# minimal-atmega32u4-arduino.net
KiCad netlist of a schematic drawn in EAGLE
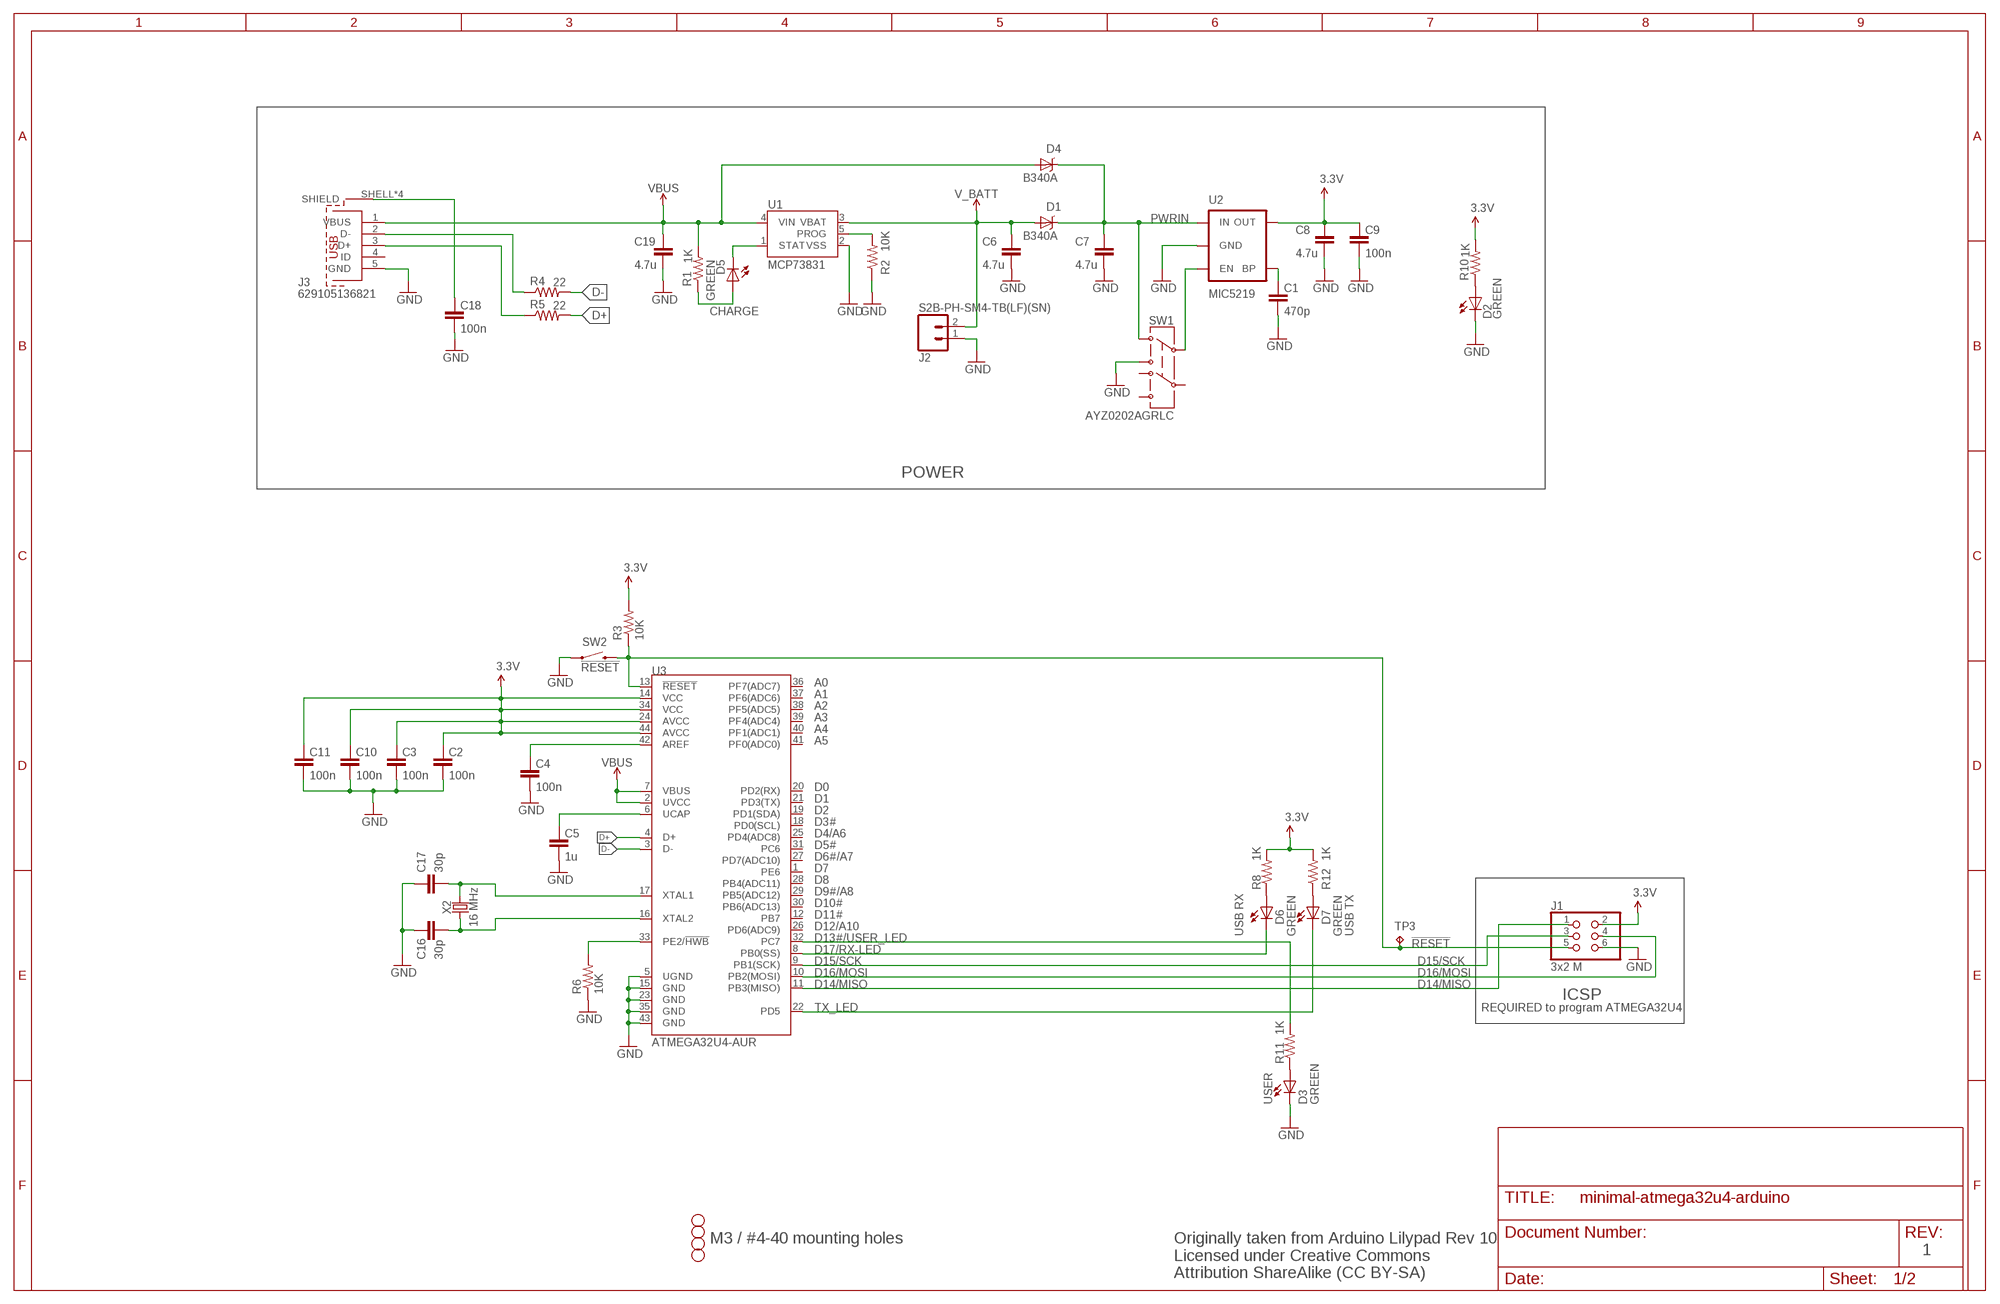
[diagram p0: schematic, sheet 1]

(export (version "E")
  (design (tool "Eeschema 10.0.6"))
  (components
    (comp (ref "C1")
      (value "470p")
      (footprint "eagle-import:C0805K")
      (fields (field (name "MFR") "Samsung") (field (name "MPN") "CL21B471KBANNNC"))
      (libsource (lib "eagle-import") (part "C-EUC0805K"))
    )
    (comp (ref "C2")
      (value "100n")
      (footprint "eagle-import:C0805K")
      (fields (field (name "MFR") "Samsung") (field (name "MPN") "CL21B104KBCNNNC"))
      (libsource (lib "eagle-import") (part "C-EUC0805K"))
    )
    (comp (ref "C3")
      (value "100n")
      (footprint "eagle-import:C0805K")
      (fields (field (name "MFR") "Samsung") (field (name "MPN") "CL21B104KBCNNNC"))
      (libsource (lib "eagle-import") (part "C-EUC0805K"))
    )
    (comp (ref "C4")
      (value "100n")
      (footprint "eagle-import:C0805K")
      (fields (field (name "MFR") "Samsung") (field (name "MPN") "CL21B104KBCNNNC"))
      (libsource (lib "eagle-import") (part "C-EUC0805K"))
    )
    (comp (ref "C5")
      (value "1u")
      (footprint "eagle-import:C0805K")
      (fields (field (name "MFR") "Samsung") (field (name "MPN") "CL21B105KOFNNNG"))
      (libsource (lib "eagle-import") (part "C-EUC0805K"))
    )
    (comp (ref "C6")
      (value "4.7u")
      (footprint "eagle-import:C0805K")
      (fields (field (name "MFR") "Samsung") (field (name "MPN") "CL21A475KOFNNNE"))
      (libsource (lib "eagle-import") (part "C-EUC0805K"))
    )
    (comp (ref "C7")
      (value "4.7u")
      (footprint "eagle-import:C0805K")
      (fields (field (name "MFR") "Samsung") (field (name "MPN") "CL21A475KOFNNNE"))
      (libsource (lib "eagle-import") (part "C-EUC0805K"))
    )
    (comp (ref "C8")
      (value "4.7u")
      (footprint "eagle-import:C0805K")
      (fields (field (name "MFR") "Samsung") (field (name "MPN") "CL21A475KOFNNNE"))
      (libsource (lib "eagle-import") (part "C-EUC0805K"))
    )
    (comp (ref "C9")
      (value "100n")
      (footprint "eagle-import:C0805K")
      (fields (field (name "MFR") "Samsung") (field (name "MPN") "CL21B104KBCNNNC"))
      (libsource (lib "eagle-import") (part "C-EUC0805K"))
    )
    (comp (ref "C10")
      (value "100n")
      (footprint "eagle-import:C0805K")
      (fields (field (name "MFR") "Samsung") (field (name "MPN") "CL21B104KBCNNNC"))
      (libsource (lib "eagle-import") (part "C-EUC0805K"))
    )
    (comp (ref "C11")
      (value "100n")
      (footprint "eagle-import:C0805K")
      (fields (field (name "MFR") "Samsung") (field (name "MPN") "CL21B104KBCNNNC"))
      (libsource (lib "eagle-import") (part "C-EUC0805K"))
    )
    (comp (ref "C16")
      (value "30p")
      (footprint "eagle-import:C0805K")
      (fields (field (name "MFR") "Samsung") (field (name "MPN") "CL21C300JBANNNC"))
      (libsource (lib "eagle-import") (part "C-EUC0805K"))
    )
    (comp (ref "C17")
      (value "30p")
      (footprint "eagle-import:C0805K")
      (fields (field (name "MFR") "Samsung") (field (name "MPN") "CL21C180JBANNNC"))
      (libsource (lib "eagle-import") (part "C-EUC0805K"))
    )
    (comp (ref "C18")
      (value "100n")
      (footprint "eagle-import:C0805K")
      (fields (field (name "MFR") "Samsung") (field (name "MPN") "CL21B104KBCNNNC"))
      (libsource (lib "eagle-import") (part "C-EUC0805K"))
    )
    (comp (ref "C19")
      (value "4.7u")
      (footprint "eagle-import:C0805K")
      (fields (field (name "MFR") "Samsung") (field (name "MPN") "CL21A475KOFNNNE"))
      (libsource (lib "eagle-import") (part "C-EUC0805K"))
    )
    (comp (ref "D1")
      (value "B340A")
      (footprint "eagle-import:SMA-DIODE")
      (fields (field (name "MFR") "Diodes Inc") (field (name "MPN") "B340AE-13"))
      (libsource (lib "eagle-import") (part "DIODE-SCHOTTKY_"))
    )
    (comp (ref "D2")
      (value "GREEN")
      (footprint "eagle-import:CHIP-LED0805")
      (fields (field (name "MFR") "Würth Elektronik") (field (name "MPN") "150080GS75000"))
      (libsource (lib "eagle-import") (part "LEDCHIP-LED0805"))
    )
    (comp (ref "D3")
      (value "GREEN")
      (footprint "eagle-import:CHIP-LED0805")
      (fields (field (name "MFR") "Würth Elektronik") (field (name "MPN") "150080GS75000"))
      (libsource (lib "eagle-import") (part "LEDCHIP-LED0805"))
    )
    (comp (ref "D4")
      (value "B340A")
      (footprint "eagle-import:SMA-DIODE")
      (fields (field (name "MFR") "Diodes Inc") (field (name "MPN") "B340AE-13"))
      (libsource (lib "eagle-import") (part "DIODE-SCHOTTKY_"))
    )
    (comp (ref "D5")
      (value "GREEN")
      (footprint "eagle-import:CHIP-LED0805")
      (fields (field (name "MFR") "Würth Elektronik") (field (name "MPN") "150080GS75000"))
      (libsource (lib "eagle-import") (part "LEDCHIP-LED0805"))
    )
    (comp (ref "D6")
      (value "GREEN")
      (footprint "eagle-import:CHIP-LED0805")
      (fields (field (name "MFR") "Würth Elektronik") (field (name "MPN") "150080GS75000"))
      (libsource (lib "eagle-import") (part "LEDCHIP-LED0805"))
    )
    (comp (ref "D7")
      (value "GREEN")
      (footprint "eagle-import:CHIP-LED0805")
      (fields (field (name "MFR") "Würth Elektronik") (field (name "MPN") "150080GS75000"))
      (libsource (lib "eagle-import") (part "LEDCHIP-LED0805"))
    )
    (comp (ref "H1")
      (value "STAND-OFF")
      (footprint "eagle-import:STAND-OFF")
      (libsource (lib "eagle-import") (part "STAND-OFF"))
    )
    (comp (ref "H2")
      (value "STAND-OFF")
      (footprint "eagle-import:STAND-OFF")
      (libsource (lib "eagle-import") (part "STAND-OFF"))
    )
    (comp (ref "H3")
      (value "STAND-OFF")
      (footprint "eagle-import:STAND-OFF")
      (libsource (lib "eagle-import") (part "STAND-OFF"))
    )
    (comp (ref "H4")
      (value "STAND-OFF")
      (footprint "eagle-import:STAND-OFF")
      (libsource (lib "eagle-import") (part "STAND-OFF"))
    )
    (comp (ref "J1")
      (value "3x2 M")
      (footprint "eagle-import:2X03")
      (fields (field (name "MFR") "Harwin") (field (name "MPN") "M20-9980345"))
      (libsource (lib "eagle-import") (part "PINHD-2X3"))
    )
    (comp (ref "J2")
      (value "S2B-PH-SM4-TB(LF)(SN)")
      (footprint "eagle-import:JST-2-SMD")
      (fields (field (name "MFR") "JST"))
      (libsource (lib "eagle-import") (part "M02-JST-2MM-SMT"))
    )
    (comp (ref "J3")
      (value "629105136821")
      (footprint "eagle-import:629105136821")
      (fields (field (name "MFR") "Wurth"))
      (libsource (lib "eagle-import") (part "629105136821"))
    )
    (comp (ref "R1")
      (value "1K")
      (footprint "eagle-import:R0805")
      (fields (field (name "MFR") "Yageo") (field (name "MPN") "RC0805FR-071KL"))
      (libsource (lib "eagle-import") (part "R-US_R0805"))
    )
    (comp (ref "R2")
      (value "10K")
      (footprint "eagle-import:R0805")
      (fields (field (name "MFR") "Yageo") (field (name "MPN") "RC0805FR-0710KL"))
      (libsource (lib "eagle-import") (part "R-US_R0805"))
    )
    (comp (ref "R3")
      (value "10K")
      (footprint "eagle-import:R0805")
      (fields (field (name "MFR") "Yageo") (field (name "MPN") "RC0805FR-0710KL"))
      (libsource (lib "eagle-import") (part "R-US_R0805"))
    )
    (comp (ref "R4")
      (value "22")
      (footprint "eagle-import:R0805")
      (fields (field (name "MFR") "Yageo") (field (name "MPN") "RC0805FR-0722RL"))
      (libsource (lib "eagle-import") (part "R-US_R0805"))
    )
    (comp (ref "R5")
      (value "22")
      (footprint "eagle-import:R0805")
      (fields (field (name "MFR") "Yageo") (field (name "MPN") "RC0805FR-0722RL"))
      (libsource (lib "eagle-import") (part "R-US_R0805"))
    )
    (comp (ref "R6")
      (value "10K")
      (footprint "eagle-import:R0805")
      (fields (field (name "MFR") "Yageo") (field (name "MPN") "RC0805FR-0710KL"))
      (libsource (lib "eagle-import") (part "R-US_R0805"))
    )
    (comp (ref "R8")
      (value "1K")
      (footprint "eagle-import:R0805")
      (fields (field (name "MFR") "Yageo") (field (name "MPN") "RC0805FR-071KL"))
      (libsource (lib "eagle-import") (part "R-US_R0805"))
    )
    (comp (ref "R10")
      (value "1K")
      (footprint "eagle-import:R0805")
      (fields (field (name "MFR") "Yageo") (field (name "MPN") "RC0805FR-071KL"))
      (libsource (lib "eagle-import") (part "R-US_R0805"))
    )
    (comp (ref "R11")
      (value "1K")
      (footprint "eagle-import:R0805")
      (fields (field (name "MFR") "Yageo") (field (name "MPN") "RC0805FR-071KL"))
      (libsource (lib "eagle-import") (part "R-US_R0805"))
    )
    (comp (ref "R12")
      (value "1K")
      (footprint "eagle-import:R0805")
      (fields (field (name "MFR") "Yageo") (field (name "MPN") "RC0805FR-071KL"))
      (libsource (lib "eagle-import") (part "R-US_R0805"))
    )
    (comp (ref "SW1")
      (value "AYZ0202AGRLC")
      (footprint "eagle-import:AYZ0202")
      (fields (field (name "MFR") "C&K"))
      (libsource (lib "eagle-import") (part "SWITCH-DPDTSMD"))
    )
    (comp (ref "SW2")
      (value "!RESET")
      (footprint "eagle-import:TACTILE_SWITCH_SMD")
      (fields (field (name "MFR") "C&K") (field (name "MPN") "RS-187R05A2-DS MT RT"))
      (libsource (lib "eagle-import") (part "SWITCH-MOMENTARY-2SMD"))
    )
    (comp (ref "TP3")
      (value "TPPAD1-13")
      (footprint "eagle-import:P1-13")
      (libsource (lib "eagle-import") (part "TPPAD1-13"))
    )
    (comp (ref "U1")
      (value "MCP73831")
      (footprint "eagle-import:SOT23-5")
      (fields (field (name "MFR") "Microchip") (field (name "MPN") "MCP73831T-2ACI/OT"))
      (libsource (lib "eagle-import") (part "MCP73831"))
    )
    (comp (ref "U2")
      (value "MIC5219")
      (footprint "eagle-import:SOT23-5")
      (fields (field (name "MFR") "Microchip") (field (name "MPN") "MIC5219-3.3YM5-TR"))
      (libsource (lib "eagle-import") (part "V_REG_MIC5219SMD"))
    )
    (comp (ref "U3")
      (value "ATMEGA32U4-AUR")
      (footprint "eagle-import:TQFP44")
      (fields (field (name "MFR") "Microchip") (field (name "PROD_ID") "IC-10828"))
      (libsource (lib "eagle-import") (part "ATMEGA32U4TQFP-44"))
    )
    (comp (ref "X2")
      (value "16 MHz")
      (footprint "eagle-import:HC49UP")
      (fields (field (name "MFR") "ECS") (field (name "MPN") "ECS-160-18-5PX-TR"))
      (libsource (lib "eagle-import") (part "CRYSTALSMD-HC49UP"))
    )
  )
  (nets
    (net (code "1") (name "3.3V") (class "Default")
      (node (ref "C10") (pin "1") (pinfunction "1_1") (pintype "passive"))
      (node (ref "C11") (pin "1") (pinfunction "1_1") (pintype "passive"))
      (node (ref "C2") (pin "1") (pinfunction "1_1") (pintype "passive"))
      (node (ref "C3") (pin "1") (pinfunction "1_1") (pintype "passive"))
      (node (ref "C8") (pin "1") (pinfunction "1_1") (pintype "passive"))
      (node (ref "C9") (pin "1") (pinfunction "1_1") (pintype "passive"))
      (node (ref "J1") (pin "2") (pinfunction "2_2") (pintype "passive"))
      (node (ref "R10") (pin "2") (pinfunction "2_2") (pintype "passive"))
      (node (ref "R12") (pin "2") (pinfunction "2_2") (pintype "passive"))
      (node (ref "R3") (pin "2") (pinfunction "2_2") (pintype "passive"))
      (node (ref "R8") (pin "2") (pinfunction "2_2") (pintype "passive"))
      (node (ref "U2") (pin "5") (pinfunction "OUT_5") (pintype "passive"))
      (node (ref "U3") (pin "14") (pinfunction "VCC_14") (pintype "bidirectional"))
      (node (ref "U3") (pin "24") (pinfunction "AVCC_24") (pintype "bidirectional"))
      (node (ref "U3") (pin "34") (pinfunction "VCC_34") (pintype "bidirectional"))
      (node (ref "U3") (pin "44") (pinfunction "AVCC_44") (pintype "bidirectional"))
    )
    (net (code "2") (name "D+") (class "Default")
      (node (ref "R5") (pin "2") (pinfunction "2_2") (pintype "passive"))
      (node (ref "U3") (pin "4") (pinfunction "D+_4") (pintype "bidirectional"))
    )
    (net (code "3") (name "D-") (class "Default")
      (node (ref "R4") (pin "2") (pinfunction "2_2") (pintype "passive"))
      (node (ref "U3") (pin "3") (pinfunction "D-_3") (pintype "bidirectional"))
    )
    (net (code "4") (name "D13#{slash}USER_LED") (class "Default")
      (node (ref "R11") (pin "2") (pinfunction "2_2") (pintype "passive"))
      (node (ref "U3") (pin "32") (pinfunction "PC7_32") (pintype "bidirectional"))
    )
    (net (code "5") (name "D14{slash}MISO") (class "Default")
      (node (ref "J1") (pin "1") (pinfunction "1_1") (pintype "passive"))
      (node (ref "U3") (pin "11") (pinfunction "PB3(MISO)_11") (pintype "bidirectional"))
    )
    (net (code "6") (name "D15{slash}SCK") (class "Default")
      (node (ref "J1") (pin "3") (pinfunction "3_3") (pintype "passive"))
      (node (ref "U3") (pin "9") (pinfunction "PB1(SCK)_9") (pintype "bidirectional"))
    )
    (net (code "7") (name "D16{slash}MOSI") (class "Default")
      (node (ref "J1") (pin "4") (pinfunction "4_4") (pintype "passive"))
      (node (ref "U3") (pin "10") (pinfunction "PB2(MOSI)_10") (pintype "bidirectional"))
    )
    (net (code "8") (name "D17{slash}RX-LED") (class "Default")
      (node (ref "D6") (pin "C") (pinfunction "C_C") (pintype "passive"))
      (node (ref "U3") (pin "8") (pinfunction "PB0(SS)_8") (pintype "bidirectional"))
    )
    (net (code "9") (name "GND") (class "Default")
      (node (ref "C1") (pin "2") (pinfunction "2_2") (pintype "passive"))
      (node (ref "C10") (pin "2") (pinfunction "2_2") (pintype "passive"))
      (node (ref "C11") (pin "2") (pinfunction "2_2") (pintype "passive"))
      (node (ref "C16") (pin "2") (pinfunction "2_2") (pintype "passive"))
      (node (ref "C17") (pin "2") (pinfunction "2_2") (pintype "passive"))
      (node (ref "C18") (pin "2") (pinfunction "2_2") (pintype "passive"))
      (node (ref "C19") (pin "2") (pinfunction "2_2") (pintype "passive"))
      (node (ref "C2") (pin "2") (pinfunction "2_2") (pintype "passive"))
      (node (ref "C3") (pin "2") (pinfunction "2_2") (pintype "passive"))
      (node (ref "C4") (pin "2") (pinfunction "2_2") (pintype "passive"))
      (node (ref "C5") (pin "2") (pinfunction "2_2") (pintype "passive"))
      (node (ref "C6") (pin "2") (pinfunction "2_2") (pintype "passive"))
      (node (ref "C7") (pin "2") (pinfunction "2_2") (pintype "passive"))
      (node (ref "C8") (pin "2") (pinfunction "2_2") (pintype "passive"))
      (node (ref "C9") (pin "2") (pinfunction "2_2") (pintype "passive"))
      (node (ref "D2") (pin "C") (pinfunction "C_C") (pintype "passive"))
      (node (ref "D3") (pin "C") (pinfunction "C_C") (pintype "passive"))
      (node (ref "J1") (pin "6") (pinfunction "6_6") (pintype "passive"))
      (node (ref "J2") (pin "1") (pinfunction "2_1") (pintype "passive"))
      (node (ref "J3") (pin "5") (pinfunction "GND_5") (pintype "passive"))
      (node (ref "R2") (pin "1") (pinfunction "1_1") (pintype "passive"))
      (node (ref "R6") (pin "1") (pinfunction "1_1") (pintype "passive"))
      (node (ref "SW1") (pin "3") (pinfunction "3_3") (pintype "bidirectional"))
      (node (ref "SW2") (pin "1") (pinfunction "1_1") (pintype "passive"))
      (node (ref "U1") (pin "2") (pinfunction "VSS_2") (pintype "power_in"))
      (node (ref "U2") (pin "2") (pinfunction "GND_2") (pintype "input"))
      (node (ref "U3") (pin "15") (pinfunction "GND_15") (pintype "bidirectional"))
      (node (ref "U3") (pin "23") (pinfunction "GND_23") (pintype "bidirectional"))
      (node (ref "U3") (pin "35") (pinfunction "GND_35") (pintype "bidirectional"))
      (node (ref "U3") (pin "43") (pinfunction "GND_43") (pintype "bidirectional"))
      (node (ref "U3") (pin "5") (pinfunction "UGND_5") (pintype "bidirectional"))
    )
    (net (code "10") (name "Net-(C18-Pad1)") (class "Default")
      (node (ref "C18") (pin "1") (pinfunction "1_1") (pintype "passive"))
      (node (ref "J3") (pin "SHELL") (pinfunction "SHIELD_SHELL") (pintype "passive"))
      (node (ref "J3") (pin "SHELL1") (pinfunction "SHIELD_SHELL1") (pintype "passive"))
      (node (ref "J3") (pin "SHELL2") (pinfunction "SHIELD_SHELL2") (pintype "passive"))
      (node (ref "J3") (pin "SHELL3") (pinfunction "SHIELD_SHELL3") (pintype "passive"))
    )
    (net (code "11") (name "Net-(D2-PadA)") (class "Default")
      (node (ref "D2") (pin "A") (pinfunction "A_A") (pintype "passive"))
      (node (ref "R10") (pin "1") (pinfunction "1_1") (pintype "passive"))
    )
    (net (code "12") (name "Net-(D3-PadA)") (class "Default")
      (node (ref "D3") (pin "A") (pinfunction "A_A") (pintype "passive"))
      (node (ref "R11") (pin "1") (pinfunction "1_1") (pintype "passive"))
    )
    (net (code "13") (name "Net-(D5-PadA)") (class "Default")
      (node (ref "D5") (pin "A") (pinfunction "A_A") (pintype "passive"))
      (node (ref "R1") (pin "1") (pinfunction "1_1") (pintype "passive"))
    )
    (net (code "14") (name "Net-(D6-PadA)") (class "Default")
      (node (ref "D6") (pin "A") (pinfunction "A_A") (pintype "passive"))
      (node (ref "R8") (pin "1") (pinfunction "1_1") (pintype "passive"))
    )
    (net (code "15") (name "Net-(D7-PadA)") (class "Default")
      (node (ref "D7") (pin "A") (pinfunction "A_A") (pintype "passive"))
      (node (ref "R12") (pin "1") (pinfunction "1_1") (pintype "passive"))
    )
    (net (code "16") (name "Net-(J3-D+)") (class "Default")
      (node (ref "J3") (pin "3") (pinfunction "D+_3") (pintype "passive"))
      (node (ref "R5") (pin "1") (pinfunction "1_1") (pintype "passive"))
    )
    (net (code "17") (name "Net-(J3-D-)") (class "Default")
      (node (ref "J3") (pin "2") (pinfunction "D-_2") (pintype "passive"))
      (node (ref "R4") (pin "1") (pinfunction "1_1") (pintype "passive"))
    )
    (net (code "18") (name "Net-(U1-PROG)") (class "Default")
      (node (ref "R2") (pin "2") (pinfunction "2_2") (pintype "passive"))
      (node (ref "U1") (pin "5") (pinfunction "PROG_5") (pintype "input"))
    )
    (net (code "19") (name "Net-(U1-STAT)") (class "Default")
      (node (ref "D5") (pin "C") (pinfunction "C_C") (pintype "passive"))
      (node (ref "U1") (pin "1") (pinfunction "STAT_1") (pintype "output"))
    )
    (net (code "20") (name "Net-(U2-BP)") (class "Default")
      (node (ref "C1") (pin "1") (pinfunction "1_1") (pintype "passive"))
      (node (ref "U2") (pin "4") (pinfunction "BP_4") (pintype "input"))
    )
    (net (code "21") (name "Net-(U2-EN)") (class "Default")
      (node (ref "SW1") (pin "2") (pinfunction "2_2") (pintype "bidirectional"))
      (node (ref "U2") (pin "3") (pinfunction "EN_3") (pintype "input"))
    )
    (net (code "22") (name "Net-(U3-AREF)") (class "Default")
      (node (ref "C4") (pin "1") (pinfunction "1_1") (pintype "passive"))
      (node (ref "U3") (pin "42") (pinfunction "AREF_42") (pintype "bidirectional"))
    )
    (net (code "23") (name "Net-(U3-PE2{slash}~{HWB})") (class "Default")
      (node (ref "R6") (pin "2") (pinfunction "2_2") (pintype "passive"))
      (node (ref "U3") (pin "33") (pinfunction "PE2/~{HWB}_33") (pintype "bidirectional"))
    )
    (net (code "24") (name "Net-(U3-UCAP)") (class "Default")
      (node (ref "C5") (pin "1") (pinfunction "1_1") (pintype "passive"))
      (node (ref "U3") (pin "6") (pinfunction "UCAP_6") (pintype "bidirectional"))
    )
    (net (code "25") (name "Net-(U3-XTAL1)") (class "Default")
      (node (ref "C17") (pin "1") (pinfunction "1_1") (pintype "passive"))
      (node (ref "U3") (pin "17") (pinfunction "XTAL1_17") (pintype "bidirectional"))
      (node (ref "X2") (pin "2") (pinfunction "2_2") (pintype "passive"))
    )
    (net (code "26") (name "Net-(U3-XTAL2)") (class "Default")
      (node (ref "C16") (pin "1") (pinfunction "1_1") (pintype "passive"))
      (node (ref "U3") (pin "16") (pinfunction "XTAL2_16") (pintype "bidirectional"))
      (node (ref "X2") (pin "1") (pinfunction "1_1") (pintype "passive"))
    )
    (net (code "27") (name "PWRIN") (class "Default")
      (node (ref "C7") (pin "1") (pinfunction "1_1") (pintype "passive"))
      (node (ref "D1") (pin "C") (pinfunction "C_C") (pintype "passive"))
      (node (ref "D4") (pin "C") (pinfunction "C_C") (pintype "passive"))
      (node (ref "SW1") (pin "1") (pinfunction "1_1") (pintype "bidirectional"))
      (node (ref "U2") (pin "1") (pinfunction "IN_1") (pintype "input"))
    )
    (net (code "28") (name "TX_LED") (class "Default")
      (node (ref "D7") (pin "C") (pinfunction "C_C") (pintype "passive"))
      (node (ref "U3") (pin "22") (pinfunction "PD5_22") (pintype "bidirectional"))
    )
    (net (code "29") (name "VBUS") (class "Default")
      (node (ref "C19") (pin "1") (pinfunction "1_1") (pintype "passive"))
      (node (ref "D4") (pin "A") (pinfunction "A_A") (pintype "passive"))
      (node (ref "J3") (pin "1") (pinfunction "VBUS_1") (pintype "passive"))
      (node (ref "R1") (pin "2") (pinfunction "2_2") (pintype "passive"))
      (node (ref "U1") (pin "4") (pinfunction "VIN_4") (pintype "power_in"))
      (node (ref "U3") (pin "2") (pinfunction "UVCC_2") (pintype "bidirectional"))
      (node (ref "U3") (pin "7") (pinfunction "VBUS_7") (pintype "bidirectional"))
    )
    (net (code "30") (name "V_BATT") (class "Default")
      (node (ref "C6") (pin "1") (pinfunction "1_1") (pintype "passive"))
      (node (ref "D1") (pin "A") (pinfunction "A_A") (pintype "passive"))
      (node (ref "J2") (pin "2") (pinfunction "1_2") (pintype "passive"))
      (node (ref "U1") (pin "3") (pinfunction "VBAT_3") (pintype "power_in"))
    )
    (net (code "31") (name "unconnected-(J3-ID-Pad4)") (class "Default")
      (node (ref "J3") (pin "4") (pinfunction "ID_4") (pintype "passive"))
    )
    (net (code "32") (name "unconnected-(SW1-Pad4)") (class "Default")
      (node (ref "SW1") (pin "4") (pinfunction "4_4") (pintype "bidirectional"))
    )
    (net (code "33") (name "unconnected-(SW1-Pad5)") (class "Default")
      (node (ref "SW1") (pin "5") (pinfunction "5_5") (pintype "bidirectional"))
    )
    (net (code "34") (name "unconnected-(SW1-Pad6)") (class "Default")
      (node (ref "SW1") (pin "6") (pinfunction "6_6") (pintype "bidirectional"))
    )
    (net (code "35") (name "unconnected-(U3-PB4(ADC11)-Pad28)") (class "Default")
      (node (ref "U3") (pin "28") (pinfunction "PB4(ADC11)_28") (pintype "bidirectional"))
    )
    (net (code "36") (name "unconnected-(U3-PB5(ADC12)-Pad29)") (class "Default")
      (node (ref "U3") (pin "29") (pinfunction "PB5(ADC12)_29") (pintype "bidirectional"))
    )
    (net (code "37") (name "unconnected-(U3-PB6(ADC13)-Pad30)") (class "Default")
      (node (ref "U3") (pin "30") (pinfunction "PB6(ADC13)_30") (pintype "bidirectional"))
    )
    (net (code "38") (name "unconnected-(U3-PB7-Pad12)") (class "Default")
      (node (ref "U3") (pin "12") (pinfunction "PB7_12") (pintype "bidirectional"))
    )
    (net (code "39") (name "unconnected-(U3-PC6-Pad31)") (class "Default")
      (node (ref "U3") (pin "31") (pinfunction "PC6_31") (pintype "bidirectional"))
    )
    (net (code "40") (name "unconnected-(U3-PD0(SCL)-Pad18)") (class "Default")
      (node (ref "U3") (pin "18") (pinfunction "PD0(SCL)_18") (pintype "bidirectional"))
    )
    (net (code "41") (name "unconnected-(U3-PD1(SDA)-Pad19)") (class "Default")
      (node (ref "U3") (pin "19") (pinfunction "PD1(SDA)_19") (pintype "bidirectional"))
    )
    (net (code "42") (name "unconnected-(U3-PD2(RX)-Pad20)") (class "Default")
      (node (ref "U3") (pin "20") (pinfunction "PD2(RX)_20") (pintype "bidirectional"))
    )
    (net (code "43") (name "unconnected-(U3-PD3(TX)-Pad21)") (class "Default")
      (node (ref "U3") (pin "21") (pinfunction "PD3(TX)_21") (pintype "bidirectional"))
    )
    (net (code "44") (name "unconnected-(U3-PD4(ADC8)-Pad25)") (class "Default")
      (node (ref "U3") (pin "25") (pinfunction "PD4(ADC8)_25") (pintype "bidirectional"))
    )
    (net (code "45") (name "unconnected-(U3-PD6(ADC9)-Pad26)") (class "Default")
      (node (ref "U3") (pin "26") (pinfunction "PD6(ADC9)_26") (pintype "bidirectional"))
    )
    (net (code "46") (name "unconnected-(U3-PD7(ADC10)-Pad27)") (class "Default")
      (node (ref "U3") (pin "27") (pinfunction "PD7(ADC10)_27") (pintype "bidirectional"))
    )
    (net (code "47") (name "unconnected-(U3-PE6-Pad1)") (class "Default")
      (node (ref "U3") (pin "1") (pinfunction "PE6_1") (pintype "bidirectional"))
    )
    (net (code "48") (name "unconnected-(U3-PF0(ADC0)-Pad41)") (class "Default")
      (node (ref "U3") (pin "41") (pinfunction "PF0(ADC0)_41") (pintype "bidirectional"))
    )
    (net (code "49") (name "unconnected-(U3-PF1(ADC1)-Pad40)") (class "Default")
      (node (ref "U3") (pin "40") (pinfunction "PF1(ADC1)_40") (pintype "bidirectional"))
    )
    (net (code "50") (name "unconnected-(U3-PF4(ADC4)-Pad39)") (class "Default")
      (node (ref "U3") (pin "39") (pinfunction "PF4(ADC4)_39") (pintype "bidirectional"))
    )
    (net (code "51") (name "unconnected-(U3-PF5(ADC5)-Pad38)") (class "Default")
      (node (ref "U3") (pin "38") (pinfunction "PF5(ADC5)_38") (pintype "bidirectional"))
    )
    (net (code "52") (name "unconnected-(U3-PF6(ADC6)-Pad37)") (class "Default")
      (node (ref "U3") (pin "37") (pinfunction "PF6(ADC6)_37") (pintype "bidirectional"))
    )
    (net (code "53") (name "unconnected-(U3-PF7(ADC7)-Pad36)") (class "Default")
      (node (ref "U3") (pin "36") (pinfunction "PF7(ADC7)_36") (pintype "bidirectional"))
    )
    (net (code "54") (name "~{RESET}") (class "Default")
      (node (ref "J1") (pin "5") (pinfunction "5_5") (pintype "passive"))
      (node (ref "R3") (pin "1") (pinfunction "1_1") (pintype "passive"))
      (node (ref "SW2") (pin "3") (pinfunction "2_3") (pintype "passive"))
      (node (ref "TP3") (pin "TP") (pinfunction "TP_TP") (pintype "input"))
      (node (ref "U3") (pin "13") (pinfunction "~{RESET}_13") (pintype "bidirectional"))
    )
  )
)
